# lora.net
KiCad netlist of a schematic drawn in Altium Designer
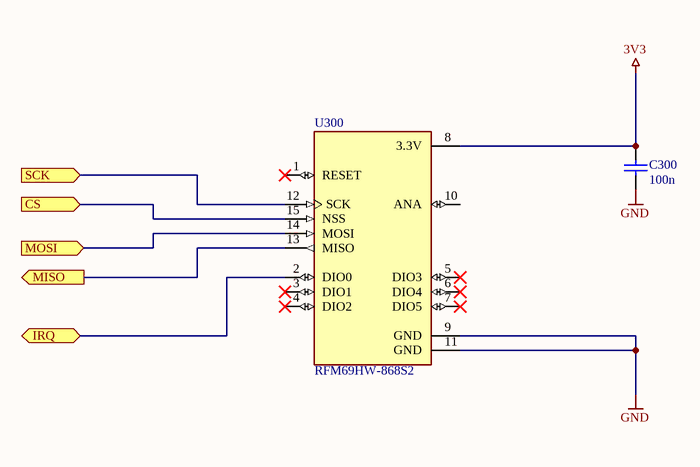
[diagram p0: lora.SchDoc]

(export (version "E")
  (design (tool "Eeschema 10.0.6"))
  (components
    (comp (ref "C300")
      (value "100n")
      (description "Capacitor")
      (libsource (lib "Simulation Generic Components") (part "Capacitor"))
    )
    (comp (ref "U300")
      (value "RFM69HW-868S2")
      (footprint "XCVR_RFM69HW-868S2")
      (description "General ISM < 1GHz Transceiver Module 868MHz Antenna Not Included Surface Mount")
      (fields (field (name "MF") "RF"))
      (libsource (lib "RFM69H") (part "RFM69HW-868S2"))
    )
  )
  (nets
    (net (code "1") (name "/CS") (class "Default")
      (node (ref "U300") (pin "15") (pinfunction "NSS_15") (pintype "input"))
    )
    (net (code "2") (name "/IRQ") (class "Default")
      (node (ref "U300") (pin "2") (pinfunction "DIO0_2") (pintype "bidirectional"))
    )
    (net (code "3") (name "/MISO") (class "Default")
      (node (ref "U300") (pin "13") (pinfunction "MISO_13") (pintype "output"))
    )
    (net (code "4") (name "/MOSI") (class "Default")
      (node (ref "U300") (pin "14") (pinfunction "MOSI_14") (pintype "input"))
    )
    (net (code "5") (name "/SCK") (class "Default")
      (node (ref "U300") (pin "12") (pinfunction "SCK_12") (pintype "input"))
    )
    (net (code "6") (name "3V3") (class "Default")
      (node (ref "C300") (pin "2") (pinfunction "2_2") (pintype "passive"))
      (node (ref "U300") (pin "8") (pinfunction "3.3V_8") (pintype "power_in"))
    )
    (net (code "7") (name "GND") (class "Default")
      (node (ref "C300") (pin "1") (pinfunction "1_1") (pintype "passive"))
      (node (ref "U300") (pin "11") (pinfunction "GND_11") (pintype "power_in"))
      (node (ref "U300") (pin "9") (pinfunction "GND_9") (pintype "power_in"))
    )
    (net (code "8") (name "unconnected-(U300-ANA-Pad10)") (class "Default")
      (node (ref "U300") (pin "10") (pinfunction "ANA_10") (pintype "bidirectional"))
    )
    (net (code "9") (name "unconnected-(U300-DIO1-Pad3)") (class "Default")
      (node (ref "U300") (pin "3") (pinfunction "DIO1_3") (pintype "bidirectional+no_connect"))
    )
    (net (code "10") (name "unconnected-(U300-DIO2-Pad4)") (class "Default")
      (node (ref "U300") (pin "4") (pinfunction "DIO2_4") (pintype "bidirectional+no_connect"))
    )
    (net (code "11") (name "unconnected-(U300-DIO3-Pad5)") (class "Default")
      (node (ref "U300") (pin "5") (pinfunction "DIO3_5") (pintype "bidirectional+no_connect"))
    )
    (net (code "12") (name "unconnected-(U300-DIO4-Pad6)") (class "Default")
      (node (ref "U300") (pin "6") (pinfunction "DIO4_6") (pintype "bidirectional+no_connect"))
    )
    (net (code "13") (name "unconnected-(U300-DIO5-Pad7)") (class "Default")
      (node (ref "U300") (pin "7") (pinfunction "DIO5_7") (pintype "bidirectional+no_connect"))
    )
    (net (code "14") (name "unconnected-(U300-RESET-Pad1)") (class "Default")
      (node (ref "U300") (pin "1") (pinfunction "RESET_1") (pintype "bidirectional+no_connect"))
    )
  )
)
